# SAME51_PINOUT.net
KiCad netlist of a schematic drawn in Altium Designer
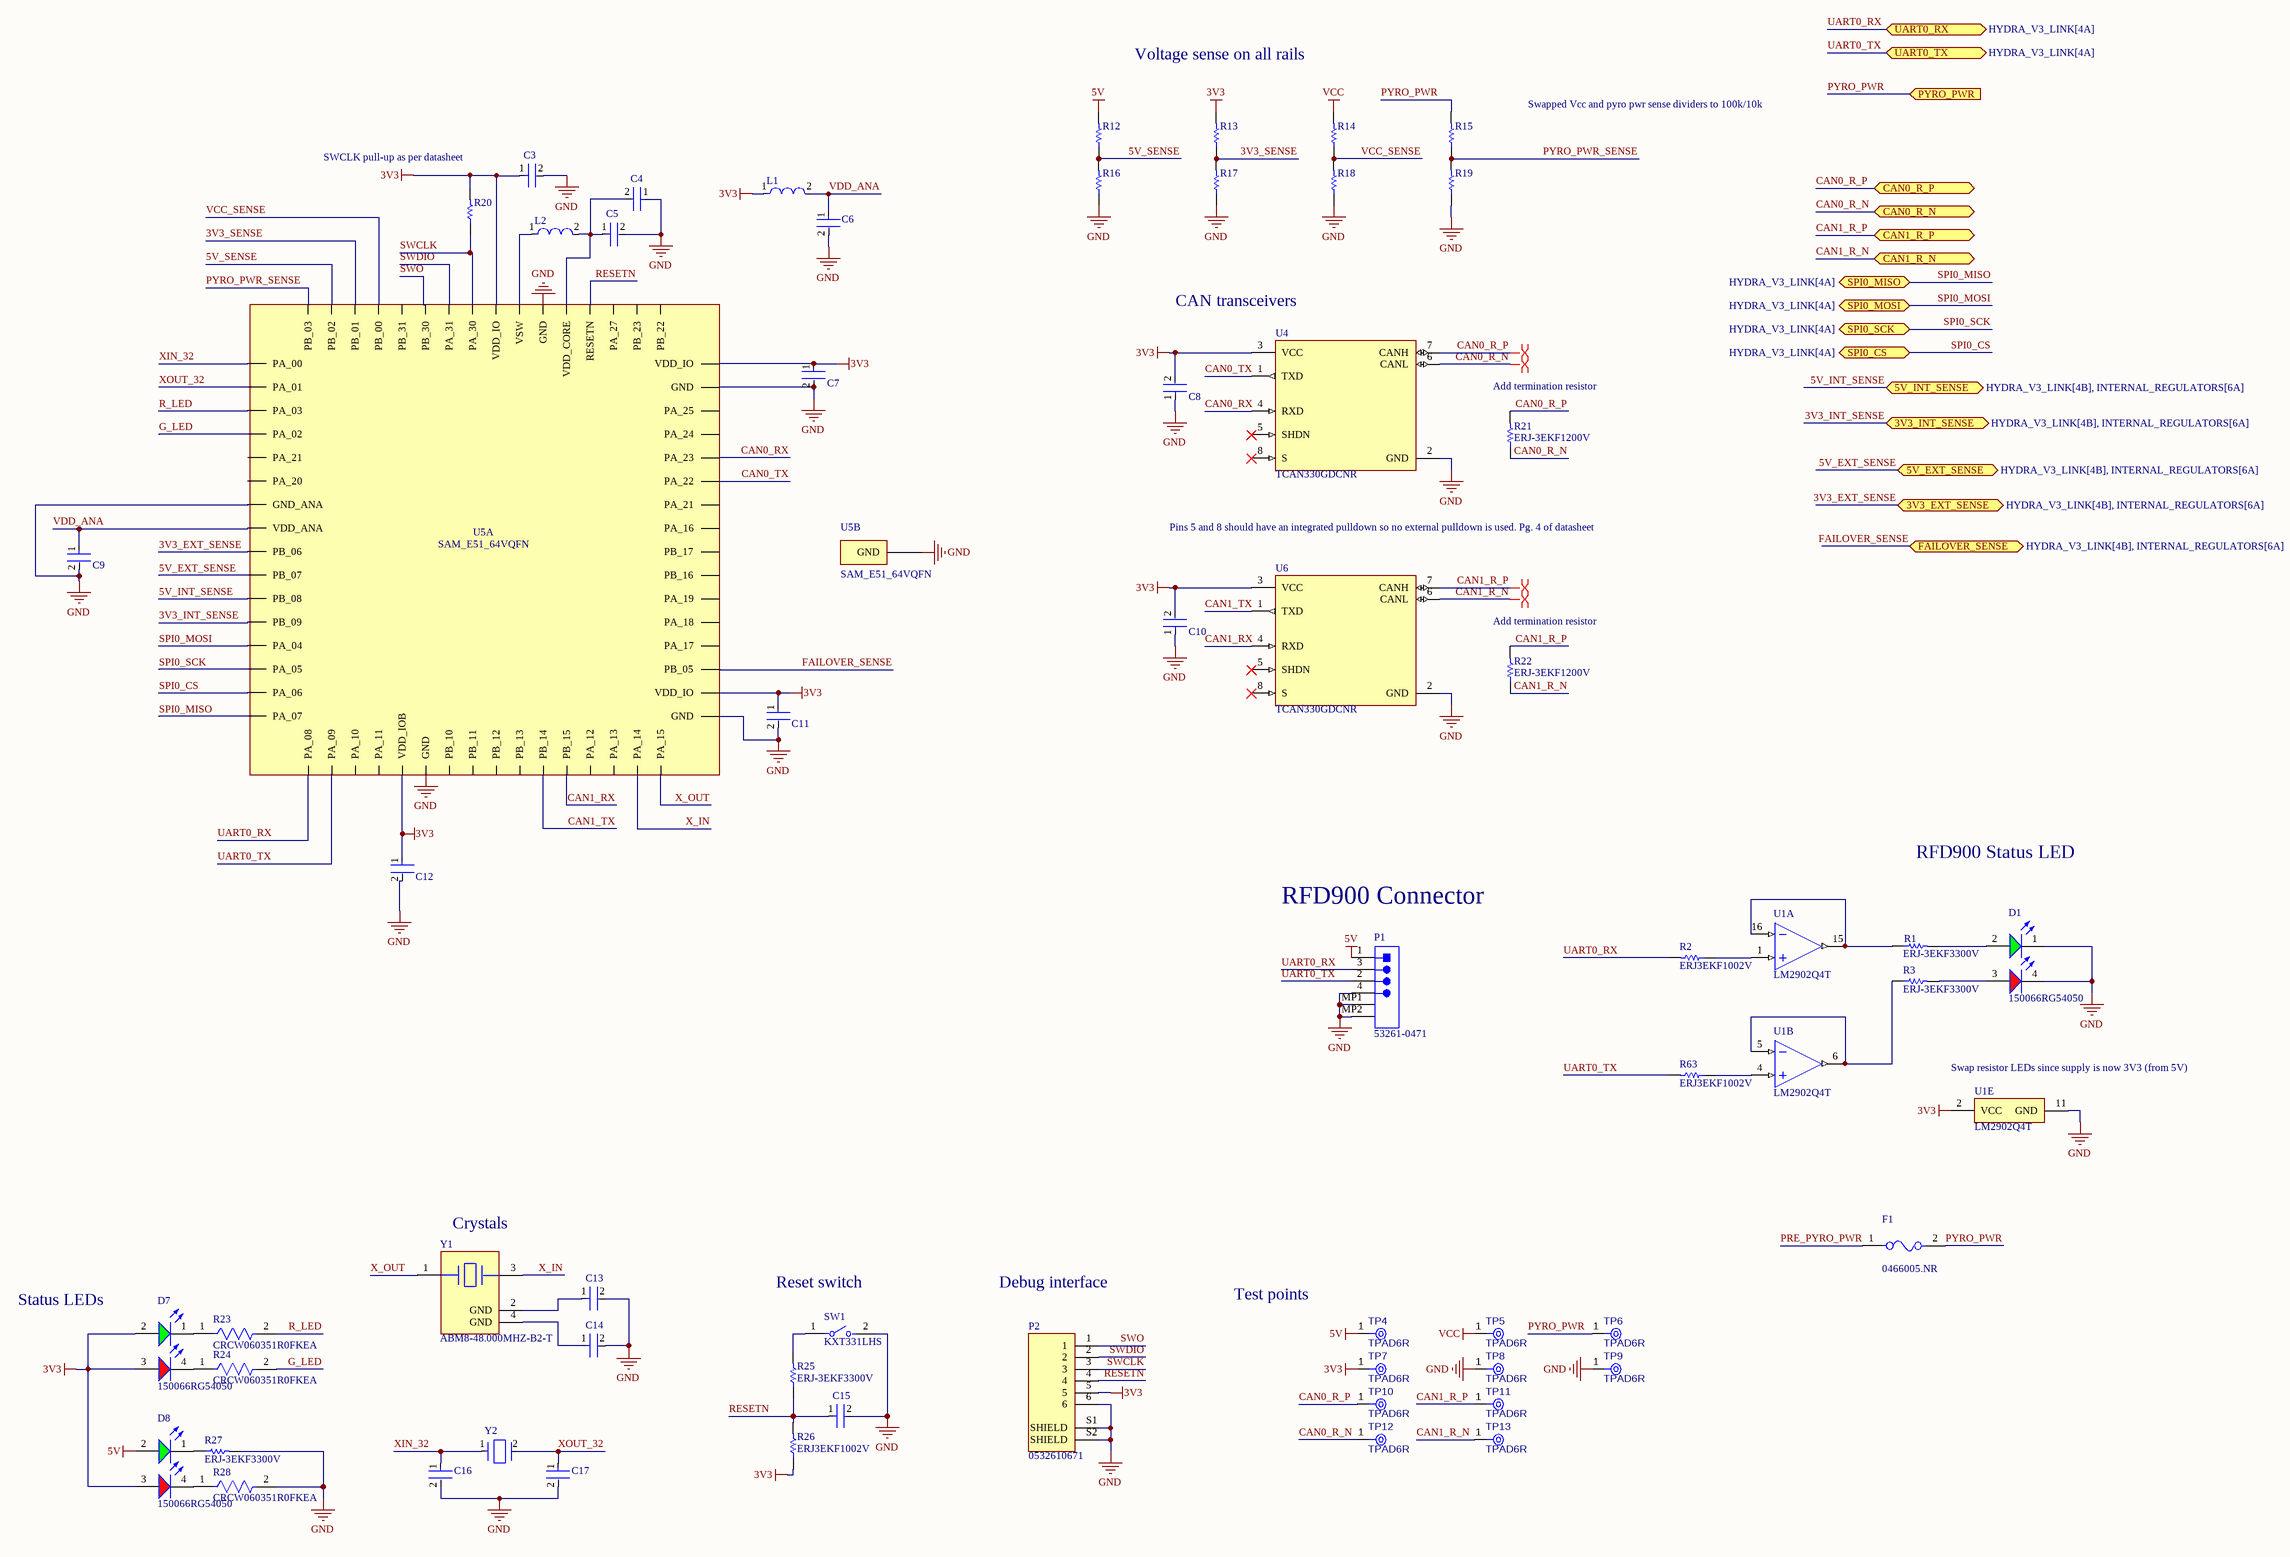
[diagram p0: SAME51_PINOUT.SchDoc]

(export (version "E")
  (design (tool "Eeschema 10.0.6"))
  (components
    (comp (ref "C3")
      (value "C0402C104K8PACTU")
      (footprint "FP-C0402-BB-MFG")
      (description "CAP CER 0.1UF 10V X5R 0402")
      (fields (field (name "MANUFACTURER") "Kemet") (field (name "TOLERANCE") "0.1"))
      (libsource (lib "Altium Content Vault") (part "b4654b650e69147ec39a6b967a45e02"))
    )
    (comp (ref "C4")
      (value "GRM155R60J475ME47D")
      (footprint "FP-GRM155-0_1-IPC_B")
      (description "Chip Multilayer Ceramic Capacitors for General Purpose, 0402, 4.7uF, X5R, 15%, 20%, 6.3V")
      (fields (field (name "VOLTAGE") "6.3V") (field (name "TOLERANCE") "20%"))
      (libsource (lib "Altium Content Vault") (part "11868f565c42a9108669ba33697ecf6"))
    )
    (comp (ref "C5")
      (value "C0402C104K8PACTU")
      (footprint "FP-C0402-BB-MFG")
      (description "CAP CER 0.1UF 10V X5R 0402")
      (fields (field (name "MANUFACTURER") "Kemet") (field (name "TOLERANCE") "0.1"))
      (libsource (lib "Altium Content Vault") (part "b4654b650e69147ec39a6b967a45e02"))
    )
    (comp (ref "C6")
      (value "C0805C106K8PACTU")
      (footprint "FP-C0805C-DG-MFG")
      (description "CAP CER 10UF 10V X5R 0805")
      (fields (field (name "TOLERANCE") "10%") (field (name "MANUFACTURER") "Kemet"))
      (libsource (lib "Altium Content Vault") (part "11868f565c42a9108669ba33697ecf6"))
    )
    (comp (ref "C7")
      (value "C0402C104K8PACTU")
      (footprint "FP-C0402-BB-MFG")
      (description "CAP CER 0.1UF 10V X5R 0402")
      (fields (field (name "MANUFACTURER") "Kemet") (field (name "TOLERANCE") "0.1"))
      (libsource (lib "Altium Content Vault") (part "b4654b650e69147ec39a6b967a45e02"))
    )
    (comp (ref "C8")
      (value "C0402C104K8PACTU")
      (footprint "FP-C0402-BB-MFG")
      (description "CAP CER 0.1UF 10V X5R 0402")
      (fields (field (name "MANUFACTURER") "Kemet") (field (name "TOLERANCE") "0.1"))
      (libsource (lib "Altium Content Vault") (part "b4654b650e69147ec39a6b967a45e02"))
    )
    (comp (ref "C9")
      (value "C0402C104K8PACTU")
      (footprint "FP-C0402-BB-MFG")
      (description "CAP CER 0.1UF 10V X5R 0402")
      (fields (field (name "MANUFACTURER") "Kemet") (field (name "TOLERANCE") "0.1"))
      (libsource (lib "Altium Content Vault") (part "b4654b650e69147ec39a6b967a45e02"))
    )
    (comp (ref "C10")
      (value "C0402C104K8PACTU")
      (footprint "FP-C0402-BB-MFG")
      (description "CAP CER 0.1UF 10V X5R 0402")
      (fields (field (name "MANUFACTURER") "Kemet") (field (name "TOLERANCE") "0.1"))
      (libsource (lib "Altium Content Vault") (part "b4654b650e69147ec39a6b967a45e02"))
    )
    (comp (ref "C11")
      (value "C0402C104K8PACTU")
      (footprint "FP-C0402-BB-MFG")
      (description "CAP CER 0.1UF 10V X5R 0402")
      (fields (field (name "MANUFACTURER") "Kemet") (field (name "TOLERANCE") "0.1"))
      (libsource (lib "Altium Content Vault") (part "b4654b650e69147ec39a6b967a45e02"))
    )
    (comp (ref "C12")
      (value "C0402C104K8PACTU")
      (footprint "FP-C0402-BB-MFG")
      (description "CAP CER 0.1UF 10V X5R 0402")
      (fields (field (name "MANUFACTURER") "Kemet") (field (name "TOLERANCE") "0.1"))
      (libsource (lib "Altium Content Vault") (part "b4654b650e69147ec39a6b967a45e02"))
    )
    (comp (ref "C13")
      (value "08051A6R8CAT2A")
      (footprint "FP-0805-L_2_01_0_2-W_1_25-MFG")
      (description "General Purpose Ceramic Capacitor, 0805, 6.8pF, 0.25pF, C0G, 30ppm/°C, 100V")
      (fields (field (name "VOLTAGE") "100V") (field (name "TOLERANCE") "5%"))
      (libsource (lib "Altium Content Vault") (part "02cd4be3c70576c341d710602a673aa"))
    )
    (comp (ref "C14")
      (value "08051A6R8CAT2A")
      (footprint "FP-0805-L_2_01_0_2-W_1_25-MFG")
      (description "General Purpose Ceramic Capacitor, 0805, 6.8pF, 0.25pF, C0G, 30ppm/°C, 100V")
      (fields (field (name "VOLTAGE") "100V") (field (name "TOLERANCE") "5%"))
      (libsource (lib "Altium Content Vault") (part "02cd4be3c70576c341d710602a673aa"))
    )
    (comp (ref "C15")
      (value "C0402C104K8PACTU")
      (footprint "FP-C0402-BB-MFG")
      (description "CAP CER 0.1UF 10V X5R 0402")
      (fields (field (name "MANUFACTURER") "Kemet") (field (name "TOLERANCE") "0.1"))
      (libsource (lib "Altium Content Vault") (part "b4654b650e69147ec39a6b967a45e02"))
    )
    (comp (ref "C16")
      (value "C0805C180J5GACTU")
      (footprint "FP-C0805C-DN-MFG")
      (description "CAP CER 18PF 50V C0G/NP0 0805")
      (fields
        (field (name "OCTOPART") "https://octopart.com/c0805c180j5gactu-kemet-144810")
        (field (name "TOLERANCE") "0.05")
      )
      (libsource (lib "Altium Content Vault") (part "b4654b650e69147ec39a6b967a45e02"))
    )
    (comp (ref "C17")
      (value "C0805C180J5GACTU")
      (footprint "FP-C0805C-DN-MFG")
      (description "CAP CER 18PF 50V C0G/NP0 0805")
      (fields
        (field (name "OCTOPART") "https://octopart.com/c0805c180j5gactu-kemet-144810")
        (field (name "TOLERANCE") "0.05")
      )
      (libsource (lib "Altium Content Vault") (part "b4654b650e69147ec39a6b967a45e02"))
    )
    (comp (ref "D1")
      (value "150066RG54050")
      (footprint "WL-SBCD_0606")
      (description "Led, Red/Grn, 180Mcd/230Mcd, 624Nm/525Nm Rohs Compliant: Yes")
      (libsource (lib "uORocketry Hardware") (part "WL-SBCD_0606_Red & Green"))
    )
    (comp (ref "D7")
      (value "150066RG54050")
      (footprint "WL-SBCD_0606")
      (description "Led, Red/Grn, 180Mcd/230Mcd, 624Nm/525Nm Rohs Compliant: Yes")
      (libsource (lib "uORocketry Hardware") (part "WL-SBCD_0606_Red & Green"))
    )
    (comp (ref "D8")
      (value "150066RG54050")
      (footprint "WL-SBCD_0606")
      (description "Led, Red/Grn, 180Mcd/230Mcd, 624Nm/525Nm Rohs Compliant: Yes")
      (libsource (lib "uORocketry Hardware") (part "WL-SBCD_0606_Red & Green"))
    )
    (comp (ref "F1")
      (value "0466005.NR")
      (footprint "FP-0466-MFG")
      (description "FUSE BOARD MNT 5A 32VAC/VDC 1206")
      (fields
        (field (name "OCTOPART") "https://octopart.com/0466005.nr-littelfuse-143206")
        (field (name "MANUFACTURER") "Littelfuse Inc")
      )
      (libsource (lib "Altium Content Vault") (part "5bcf9b9f640e542cf0359d10258e979"))
    )
    (comp (ref "L1")
      (value "NR6028T100M")
      (footprint "FP-NR6028-MFG")
      (description "SMD Power Inductors 10uH ±20% 1.9A 84.5mΩ")
      (fields (field (name "TOLERANCE") "20%"))
      (libsource (lib "Altium Content Vault") (part "725321dda6339637d4d059423bc1c3c"))
    )
    (comp (ref "L2")
      (value "NR6028T100M")
      (footprint "FP-NR6028-MFG")
      (description "SMD Power Inductors 10uH ±20% 1.9A 84.5mΩ")
      (fields (field (name "TOLERANCE") "20%"))
      (libsource (lib "Altium Content Vault") (part "725321dda6339637d4d059423bc1c3c"))
    )
    (comp (ref "P1")
      (value "53261-0471")
      (footprint "MOLEX-53261-0471_V")
      (description "Male Header, Pitch 1.25 mm, 1 x 4 Position, Height 3.4 mm, -40 to 85 degC, RoHS, Tape and Reel")
      (fields (field (name "MANUFACTURER") "Molex"))
      (libsource (lib "Altium Content Vault") (part "CN-1P-2M-R4_A"))
    )
    (comp (ref "P2")
      (value "0532610671")
      (footprint "0532610671-Footprint-1")
      (description "Conn Shrouded Header (4 Sides) HDR 6 POS 1.25mm Solder RA Side Entry SMD PicoBlade™ T/R")
      (libsource (lib "uORocketry Hardware") (part "0532610671"))
    )
    (comp (ref "R1")
      (value "ERJ-3EKF3300V")
      (footprint "RESC1608X55X30LL15T15")
      (description "Chip Resistor, 330 Ohm, +/- 1%, 0.1 W, -55 to 155 degC, 0603 (1608 Metric), RoHS, Tape and Reel")
      (libsource (lib "Altium Content Vault") (part "RES-2"))
    )
    (comp (ref "R2")
      (value "ERJ3EKF1002V")
      (footprint "RESC1609X55X30LL15T15")
      (description "Chip Resistor, 10 KOhm, +/- 1%, 0.1 W, -55 to 155 degC, 0603 (1608 Metric), RoHS, Tape and Reel")
      (fields (field (name "TOLERANCE") "1%") (field (name "MANUFACTURER") "Panasonic"))
      (libsource (lib "Altium Content Vault") (part "RES-2"))
    )
    (comp (ref "R3")
      (value "ERJ-3EKF3300V")
      (footprint "RESC1608X55X30LL15T15")
      (description "Chip Resistor, 330 Ohm, +/- 1%, 0.1 W, -55 to 155 degC, 0603 (1608 Metric), RoHS, Tape and Reel")
      (libsource (lib "Altium Content Vault") (part "RES-2"))
    )
    (comp (ref "R12")
      (value "ERJ3EKF1002V")
      (footprint "RESC1609X55X30LL15T15")
      (description "Chip Resistor, 10 KOhm, +/- 1%, 0.1 W, -55 to 155 degC, 0603 (1608 Metric), RoHS, Tape and Reel")
      (fields (field (name "TOLERANCE") "1%") (field (name "MANUFACTURER") "Panasonic"))
      (libsource (lib "Altium Content Vault") (part "RES-2"))
    )
    (comp (ref "R13")
      (value "ERJ3EKF1002V")
      (footprint "RESC1609X55X30LL15T15")
      (description "Chip Resistor, 10 KOhm, +/- 1%, 0.1 W, -55 to 155 degC, 0603 (1608 Metric), RoHS, Tape and Reel")
      (fields (field (name "TOLERANCE") "1%") (field (name "MANUFACTURER") "Panasonic"))
      (libsource (lib "Altium Content Vault") (part "RES-2"))
    )
    (comp (ref "R14")
      (value "ERJ-3EKF1003V")
      (footprint "RESC1608X55X30ML15T15")
      (fields (field (name "MANUFACTURER") "Panasonic"))
      (libsource (lib "Altium Content Vault") (part "RES"))
    )
    (comp (ref "R15")
      (value "ERJ-3EKF1003V")
      (footprint "RESC1608X55X30ML15T15")
      (fields (field (name "MANUFACTURER") "Panasonic"))
      (libsource (lib "Altium Content Vault") (part "RES"))
    )
    (comp (ref "R16")
      (value "ERJ3EKF1002V")
      (footprint "RESC1609X55X30LL15T15")
      (description "Chip Resistor, 10 KOhm, +/- 1%, 0.1 W, -55 to 155 degC, 0603 (1608 Metric), RoHS, Tape and Reel")
      (fields (field (name "TOLERANCE") "1%") (field (name "MANUFACTURER") "Panasonic"))
      (libsource (lib "Altium Content Vault") (part "RES-2"))
    )
    (comp (ref "R17")
      (value "ERJ3EKF1002V")
      (footprint "RESC1609X55X30LL15T15")
      (description "Chip Resistor, 10 KOhm, +/- 1%, 0.1 W, -55 to 155 degC, 0603 (1608 Metric), RoHS, Tape and Reel")
      (fields (field (name "TOLERANCE") "1%") (field (name "MANUFACTURER") "Panasonic"))
      (libsource (lib "Altium Content Vault") (part "RES-2"))
    )
    (comp (ref "R18")
      (value "ERJ3EKF1002V")
      (footprint "RESC1609X55X30LL15T15")
      (description "Chip Resistor, 10 KOhm, +/- 1%, 0.1 W, -55 to 155 degC, 0603 (1608 Metric), RoHS, Tape and Reel")
      (fields (field (name "TOLERANCE") "1%") (field (name "MANUFACTURER") "Panasonic"))
      (libsource (lib "Altium Content Vault") (part "RES-2"))
    )
    (comp (ref "R19")
      (value "ERJ3EKF1002V")
      (footprint "RESC1609X55X30LL15T15")
      (description "Chip Resistor, 10 KOhm, +/- 1%, 0.1 W, -55 to 155 degC, 0603 (1608 Metric), RoHS, Tape and Reel")
      (fields (field (name "TOLERANCE") "1%") (field (name "MANUFACTURER") "Panasonic"))
      (libsource (lib "Altium Content Vault") (part "RES-2"))
    )
    (comp (ref "R20")
      (value "ERJ3EKF1002V")
      (footprint "RESC1609X55X30LL15T15")
      (description "Chip Resistor, 10 KOhm, +/- 1%, 0.1 W, -55 to 155 degC, 0603 (1608 Metric), RoHS, Tape and Reel")
      (fields (field (name "TOLERANCE") "1%") (field (name "MANUFACTURER") "Panasonic"))
      (libsource (lib "Altium Content Vault") (part "RES-2"))
    )
    (comp (ref "R21")
      (value "ERJ-3EKF1200V")
      (footprint "RESC1609X55X30ML15T15")
      (description "Chip Resistor, 120 Ohm, +/- 1%, 0.1 W, -55 to 155 degC, 0603 (1608 Metric), RoHS, Tape and Reel")
      (fields (field (name "TOLERANCE") "1%") (field (name "MANUFACTURER") "Panasonic"))
      (libsource (lib "Altium Content Vault") (part "RES-2"))
    )
    (comp (ref "R22")
      (value "ERJ-3EKF1200V")
      (footprint "RESC1609X55X30ML15T15")
      (description "Chip Resistor, 120 Ohm, +/- 1%, 0.1 W, -55 to 155 degC, 0603 (1608 Metric), RoHS, Tape and Reel")
      (fields (field (name "TOLERANCE") "1%") (field (name "MANUFACTURER") "Panasonic"))
      (libsource (lib "Altium Content Vault") (part "RES-2"))
    )
    (comp (ref "R23")
      (value "CRCW060351R0FKEA")
      (footprint "FP-CRCW0603-e3-MFG")
      (description "RES Thick Film, 51Ω, 1%, 0.1W, 100ppm/°C, 0603")
      (fields (field (name "TOLERANCE") "1%"))
      (libsource (lib "Altium Content Vault") (part "1029c3af85768c4190bb7ad29bc67b5"))
    )
    (comp (ref "R24")
      (value "CRCW060351R0FKEA")
      (footprint "FP-CRCW0603-e3-MFG")
      (description "RES Thick Film, 51Ω, 1%, 0.1W, 100ppm/°C, 0603")
      (fields (field (name "TOLERANCE") "1%"))
      (libsource (lib "Altium Content Vault") (part "1029c3af85768c4190bb7ad29bc67b5"))
    )
    (comp (ref "R25")
      (value "ERJ-3EKF3300V")
      (footprint "RESC1608X55X30LL15T15")
      (description "Chip Resistor, 330 Ohm, +/- 1%, 0.1 W, -55 to 155 degC, 0603 (1608 Metric), RoHS, Tape and Reel")
      (libsource (lib "Altium Content Vault") (part "RES-2"))
    )
    (comp (ref "R26")
      (value "ERJ3EKF1002V")
      (footprint "RESC1609X55X30LL15T15")
      (description "Chip Resistor, 10 KOhm, +/- 1%, 0.1 W, -55 to 155 degC, 0603 (1608 Metric), RoHS, Tape and Reel")
      (fields (field (name "TOLERANCE") "1%") (field (name "MANUFACTURER") "Panasonic"))
      (libsource (lib "Altium Content Vault") (part "RES-2"))
    )
    (comp (ref "R27")
      (value "ERJ-3EKF3300V")
      (footprint "RESC1608X55X30LL15T15")
      (description "Chip Resistor, 330 Ohm, +/- 1%, 0.1 W, -55 to 155 degC, 0603 (1608 Metric), RoHS, Tape and Reel")
      (libsource (lib "Altium Content Vault") (part "RES-2"))
    )
    (comp (ref "R28")
      (value "CRCW060351R0FKEA")
      (footprint "FP-CRCW0603-e3-MFG")
      (description "RES Thick Film, 51Ω, 1%, 0.1W, 100ppm/°C, 0603")
      (fields (field (name "TOLERANCE") "1%"))
      (libsource (lib "Altium Content Vault") (part "1029c3af85768c4190bb7ad29bc67b5"))
    )
    (comp (ref "R63")
      (value "ERJ3EKF1002V")
      (footprint "RESC1609X55X30LL15T15")
      (description "Chip Resistor, 10 KOhm, +/- 1%, 0.1 W, -55 to 155 degC, 0603 (1608 Metric), RoHS, Tape and Reel")
      (fields (field (name "TOLERANCE") "1%") (field (name "MANUFACTURER") "Panasonic"))
      (libsource (lib "Altium Content Vault") (part "RES-2"))
    )
    (comp (ref "SW1")
      (value "KXT331LHS")
      (footprint "FP-KXT331LHS-MFG")
      (description "SWITCH TACTILE SPST-NO 0.02A 15V")
      (libsource (lib "Altium Content Vault") (part "bb27bde45df87f1f469753f287ef5ae"))
    )
    (comp (ref "TP4")
      (value "TPAD6R")
      (footprint "TP06R")
      (description "0.6mm round")
      (libsource (lib "uORocketry Hardware") (part "CMP-001-0001-4"))
    )
    (comp (ref "TP5")
      (value "TPAD6R")
      (footprint "TP06R")
      (description "0.6mm round")
      (libsource (lib "uORocketry Hardware") (part "CMP-001-0001-4"))
    )
    (comp (ref "TP6")
      (value "TPAD6R")
      (footprint "TP06R")
      (description "0.6mm round")
      (libsource (lib "uORocketry Hardware") (part "CMP-001-0001-4"))
    )
    (comp (ref "TP7")
      (value "TPAD6R")
      (footprint "TP06R")
      (description "0.6mm round")
      (libsource (lib "uORocketry Hardware") (part "CMP-001-0001-4"))
    )
    (comp (ref "TP8")
      (value "TPAD6R")
      (footprint "TP06R")
      (description "0.6mm round")
      (libsource (lib "uORocketry Hardware") (part "CMP-001-0001-4"))
    )
    (comp (ref "TP9")
      (value "TPAD6R")
      (footprint "TP06R")
      (description "0.6mm round")
      (libsource (lib "uORocketry Hardware") (part "CMP-001-0001-4"))
    )
    (comp (ref "TP10")
      (value "TPAD6R")
      (footprint "TP06R")
      (description "0.6mm round")
      (libsource (lib "uORocketry Hardware") (part "CMP-001-0001-4"))
    )
    (comp (ref "TP11")
      (value "TPAD6R")
      (footprint "TP06R")
      (description "0.6mm round")
      (libsource (lib "uORocketry Hardware") (part "CMP-001-0001-4"))
    )
    (comp (ref "TP12")
      (value "TPAD6R")
      (footprint "TP06R")
      (description "0.6mm round")
      (libsource (lib "uORocketry Hardware") (part "CMP-001-0001-4"))
    )
    (comp (ref "TP13")
      (value "TPAD6R")
      (footprint "TP06R")
      (description "0.6mm round")
      (libsource (lib "uORocketry Hardware") (part "CMP-001-0001-4"))
    )
    (comp (ref "U1")
      (value "LM2902Q4T")
      (footprint "LM2902Q4T-Footprint-1")
      (description "LM2902 Series 30 V 1.3 MHz Low-Power Quad Operational Amplifier - QFN-16 (3x3)")
      (libsource (lib "uORocketry Hardware") (part "LM2902Q4T"))
    )
    (comp (ref "U4")
      (value "TCAN330GDCNR")
      (footprint "FP-DCN0008A-MFG")
      (description "IC TRANSCEIVER 1/1 SOT23-8")
      (libsource (lib "Altium Content Vault") (part "22681b49c22ad38c6a4e12e04c36c7a"))
    )
    (comp (ref "U5")
      (value "SAM_E51_64VQFN")
      (footprint "SAM_E51_64VQFN-Footprint-1")
      (description "Rudimentary symbol and footprint for the SAM E51 microcontroller")
      (libsource (lib "") (part "SAM_E51_64VQFN-Symbol-1_1"))
    )
    (comp (ref "U6")
      (value "TCAN330GDCNR")
      (footprint "FP-DCN0008A-MFG")
      (description "IC TRANSCEIVER 1/1 SOT23-8")
      (libsource (lib "Altium Content Vault") (part "22681b49c22ad38c6a4e12e04c36c7a"))
    )
    (comp (ref "Y1")
      (value "ABM8-48.000MHZ-B2-T")
      (footprint "FP-ABM8-MFG")
      (description "Crystal 48MHz ±20ppm 18pF SMD-4 3.2mm x 2.5mm")
      (fields (field (name "TOLERANCE") "20ppm"))
      (libsource (lib "Altium Content Vault") (part "dfdb7f9a12507849fb681da9a70121c"))
    )
    (comp (ref "Y2")
      (value "ECS-.327-12.5-1210-TR")
      (footprint "FP-ECX-1210-MFG")
      (description "CRYSTAL 32.7680KHZ 12.5PF SMD")
      (fields
        (field (name "OCTOPART") "https://octopart.com/ecs-.327-12.5-1210-tr-ecs+international-81221340")
        (field (name "TOLERANCE") "20ppm")
      )
      (libsource (lib "Altium Content Vault") (part "99724985039315a44fd0d1401b84e49"))
    )
  )
  (nets
    (net (code "1") (name "/3V3_EXT_SENSE") (class "Default")
      (node (ref "U5") (pin "9") (pinfunction "PB_06_9") (pintype "passive"))
    )
    (net (code "2") (name "/3V3_INT_SENSE") (class "Default")
      (node (ref "U5") (pin "12") (pinfunction "PB_09_12") (pintype "passive"))
    )
    (net (code "3") (name "/3V3_SENSE") (class "Default")
      (node (ref "R13") (pin "1") (pinfunction "1_1") (pintype "passive"))
      (node (ref "R17") (pin "2") (pinfunction "2_2") (pintype "passive"))
      (node (ref "U5") (pin "62") (pinfunction "PB_01_62") (pintype "passive"))
    )
    (net (code "4") (name "/5V_EXT_SENSE") (class "Default")
      (node (ref "U5") (pin "10") (pinfunction "PB_07_10") (pintype "passive"))
    )
    (net (code "5") (name "/5V_INT_SENSE") (class "Default")
      (node (ref "U5") (pin "11") (pinfunction "PB_08_11") (pintype "passive"))
    )
    (net (code "6") (name "/5V_SENSE") (class "Default")
      (node (ref "R12") (pin "1") (pinfunction "1_1") (pintype "passive"))
      (node (ref "R16") (pin "2") (pinfunction "2_2") (pintype "passive"))
      (node (ref "U5") (pin "63") (pinfunction "PB_02_63") (pintype "passive"))
    )
    (net (code "8") (name "/CAN0_RX") (class "Default")
      (node (ref "U4") (pin "4") (pinfunction "RXD_4") (pintype "input"))
      (node (ref "U5") (pin "44") (pinfunction "PA_23_44") (pintype "passive"))
    )
    (net (code "9") (name "/CAN0_R_N") (class "Default")
      (node (ref "R21") (pin "1") (pinfunction "1_1") (pintype "passive"))
      (node (ref "TP12") (pin "1") (pinfunction "TP_1") (pintype "passive"))
      (node (ref "U4") (pin "6") (pinfunction "CANL_6") (pintype "bidirectional"))
    )
    (net (code "10") (name "/CAN0_R_P") (class "Default")
      (node (ref "R21") (pin "2") (pinfunction "2_2") (pintype "passive"))
      (node (ref "TP10") (pin "1") (pinfunction "TP_1") (pintype "passive"))
      (node (ref "U4") (pin "7") (pinfunction "CANH_7") (pintype "bidirectional"))
    )
    (net (code "11") (name "/CAN0_TX") (class "Default")
      (node (ref "U4") (pin "1") (pinfunction "TXD_1") (pintype "output"))
      (node (ref "U5") (pin "43") (pinfunction "PA_22_43") (pintype "passive"))
    )
    (net (code "12") (name "/CAN1_RX") (class "Default")
      (node (ref "U5") (pin "28") (pinfunction "PB_15_28") (pintype "passive"))
      (node (ref "U6") (pin "4") (pinfunction "RXD_4") (pintype "input"))
    )
    (net (code "13") (name "/CAN1_R_N") (class "Default")
      (node (ref "R22") (pin "1") (pinfunction "1_1") (pintype "passive"))
      (node (ref "TP13") (pin "1") (pinfunction "TP_1") (pintype "passive"))
      (node (ref "U6") (pin "6") (pinfunction "CANL_6") (pintype "bidirectional"))
    )
    (net (code "14") (name "/CAN1_R_P") (class "Default")
      (node (ref "R22") (pin "2") (pinfunction "2_2") (pintype "passive"))
      (node (ref "TP11") (pin "1") (pinfunction "TP_1") (pintype "passive"))
      (node (ref "U6") (pin "7") (pinfunction "CANH_7") (pintype "bidirectional"))
    )
    (net (code "15") (name "/CAN1_TX") (class "Default")
      (node (ref "U5") (pin "27") (pinfunction "PB_14_27") (pintype "passive"))
      (node (ref "U6") (pin "1") (pinfunction "TXD_1") (pintype "output"))
    )
    (net (code "16") (name "/FAILOVER_SENSE") (class "Default")
      (node (ref "U5") (pin "6") (pinfunction "PB_05_6") (pintype "passive"))
    )
    (net (code "17") (name "/G_LED") (class "Default")
      (node (ref "R24") (pin "2") (pinfunction "2_2") (pintype "passive"))
      (node (ref "U5") (pin "3") (pinfunction "PA_02_3") (pintype "passive"))
    )
    (net (code "18") (name "/PRE_PYRO_PWR") (class "Default")
      (node (ref "F1") (pin "1") (pinfunction "1_1") (pintype "passive"))
    )
    (net (code "19") (name "/PYRO_PWR") (class "Default")
      (node (ref "F1") (pin "2") (pinfunction "2_2") (pintype "passive"))
      (node (ref "R15") (pin "2") (pinfunction "2_2") (pintype "passive"))
      (node (ref "TP6") (pin "1") (pinfunction "TP_1") (pintype "passive"))
    )
    (net (code "20") (name "/PYRO_PWR_SENSE") (class "Default")
      (node (ref "R15") (pin "1") (pinfunction "1_1") (pintype "passive"))
      (node (ref "R19") (pin "2") (pinfunction "2_2") (pintype "passive"))
      (node (ref "U5") (pin "64") (pinfunction "PB_03_64") (pintype "passive"))
    )
    (net (code "21") (name "/RESETN") (class "Default")
      (node (ref "C15") (pin "1") (pinfunction "1_1") (pintype "passive"))
      (node (ref "P2") (pin "4") (pinfunction "4_4") (pintype "passive"))
      (node (ref "R25") (pin "1") (pinfunction "1_1") (pintype "passive"))
      (node (ref "R26") (pin "2") (pinfunction "2_2") (pintype "passive"))
      (node (ref "U5") (pin "52") (pinfunction "RESETN_52") (pintype "passive"))
    )
    (net (code "22") (name "/R_LED") (class "Default")
      (node (ref "R23") (pin "2") (pinfunction "2_2") (pintype "passive"))
      (node (ref "U5") (pin "4") (pinfunction "PA_03_4") (pintype "passive"))
    )
    (net (code "23") (name "/SPI0_CS") (class "Default")
      (node (ref "U5") (pin "15") (pinfunction "PA_06_15") (pintype "passive"))
    )
    (net (code "24") (name "/SPI0_MISO") (class "Default")
      (node (ref "U5") (pin "16") (pinfunction "PA_07_16") (pintype "passive"))
    )
    (net (code "25") (name "/SPI0_MOSI") (class "Default")
      (node (ref "U5") (pin "13") (pinfunction "PA_04_13") (pintype "passive"))
    )
    (net (code "26") (name "/SPI0_SCK") (class "Default")
      (node (ref "U5") (pin "14") (pinfunction "PA_05_14") (pintype "passive"))
    )
    (net (code "27") (name "/SWCLK") (class "Default")
      (node (ref "P2") (pin "3") (pinfunction "3_3") (pintype "passive"))
      (node (ref "R20") (pin "1") (pinfunction "1_1") (pintype "passive"))
      (node (ref "U5") (pin "57") (pinfunction "PA_30_57") (pintype "passive"))
    )
    (net (code "28") (name "/SWDIO") (class "Default")
      (node (ref "P2") (pin "2") (pinfunction "2_2") (pintype "passive"))
      (node (ref "U5") (pin "58") (pinfunction "PA_31_58") (pintype "passive"))
    )
    (net (code "29") (name "/SWO") (class "Default")
      (node (ref "P2") (pin "1") (pinfunction "1_1") (pintype "passive"))
      (node (ref "U5") (pin "59") (pinfunction "PB_30_59") (pintype "passive"))
    )
    (net (code "30") (name "/UART0_RX") (class "Default")
      (node (ref "P1") (pin "3") (pinfunction "3_3") (pintype "passive"))
      (node (ref "R2") (pin "2") (pinfunction "2_2") (pintype "passive"))
      (node (ref "U5") (pin "17") (pinfunction "PA_08_17") (pintype "passive"))
    )
    (net (code "31") (name "/UART0_TX") (class "Default")
      (node (ref "P1") (pin "2") (pinfunction "2_2") (pintype "passive"))
      (node (ref "R63") (pin "2") (pinfunction "2_2") (pintype "passive"))
      (node (ref "U5") (pin "18") (pinfunction "PA_09_18") (pintype "passive"))
    )
    (net (code "32") (name "/VCC_SENSE") (class "Default")
      (node (ref "R14") (pin "1") (pinfunction "1_1") (pintype "passive"))
      (node (ref "R18") (pin "2") (pinfunction "2_2") (pintype "passive"))
      (node (ref "U5") (pin "61") (pinfunction "PB_00_61") (pintype "passive"))
    )
    (net (code "33") (name "/VDD_ANA") (class "Default")
      (node (ref "C6") (pin "1") (pinfunction "1_1") (pintype "passive"))
      (node (ref "C9") (pin "1") (pinfunction "1_1") (pintype "passive"))
      (node (ref "L1") (pin "2") (pinfunction "2_2") (pintype "passive"))
      (node (ref "U5") (pin "8") (pinfunction "VDD_ANA_8") (pintype "passive"))
    )
    (net (code "34") (name "/XIN_32") (class "Default")
      (node (ref "C16") (pin "1") (pinfunction "1_1") (pintype "passive"))
      (node (ref "U5") (pin "1") (pinfunction "PA_00_1") (pintype "passive"))
      (node (ref "Y2") (pin "1") (pinfunction "In/Out_1") (pintype "passive"))
    )
    (net (code "35") (name "/XOUT_32") (class "Default")
      (node (ref "C17") (pin "1") (pinfunction "1_1") (pintype "passive"))
      (node (ref "U5") (pin "2") (pinfunction "PA_01_2") (pintype "passive"))
      (node (ref "Y2") (pin "2") (pinfunction "Out/In_2") (pintype "passive"))
    )
    (net (code "36") (name "/X_IN") (class "Default")
      (node (ref "U5") (pin "31") (pinfunction "PA_14_31") (pintype "passive"))
      (node (ref "Y1") (pin "3") (pinfunction "3_3") (pintype "passive"))
    )
    (net (code "37") (name "/X_OUT") (class "Default")
      (node (ref "U5") (pin "32") (pinfunction "PA_15_32") (pintype "passive"))
      (node (ref "Y1") (pin "1") (pinfunction "1_1") (pintype "passive"))
    )
    (net (code "38") (name "3V3") (class "Default")
      (node (ref "C10") (pin "2") (pinfunction "2_2") (pintype "passive"))
      (node (ref "C11") (pin "1") (pinfunction "1_1") (pintype "passive"))
      (node (ref "C12") (pin "1") (pinfunction "1_1") (pintype "passive"))
      (node (ref "C3") (pin "1") (pinfunction "1_1") (pintype "passive"))
      (node (ref "C7") (pin "1") (pinfunction "1_1") (pintype "passive"))
      (node (ref "C8") (pin "2") (pinfunction "2_2") (pintype "passive"))
      (node (ref "D7") (pin "2") (pinfunction "A_2") (pintype "passive"))
      (node (ref "D7") (pin "3") (pinfunction "A_3") (pintype "passive"))
      (node (ref "D8") (pin "3") (pinfunction "A_3") (pintype "passive"))
      (node (ref "L1") (pin "1") (pinfunction "1_1") (pintype "passive"))
      (node (ref "P2") (pin "5") (pinfunction "5_5") (pintype "passive"))
      (node (ref "R13") (pin "2") (pinfunction "2_2") (pintype "passive"))
      (node (ref "R20") (pin "2") (pinfunction "2_2") (pintype "passive"))
      (node (ref "R26") (pin "1") (pinfunction "1_1") (pintype "passive"))
      (node (ref "TP7") (pin "1") (pinfunction "TP_1") (pintype "passive"))
      (node (ref "U1") (pin "2") (pinfunction "VCC_2") (pintype "power_in"))
      (node (ref "U4") (pin "3") (pinfunction "VCC_3") (pintype "power_in"))
      (node (ref "U5") (pin "21") (pinfunction "VDD_IOB_21") (pintype "passive"))
      (node (ref "U5") (pin "34") (pinfunction "VDD_IO_34") (pintype "passive"))
      (node (ref "U5") (pin "48") (pinfunction "VDD_IO_48") (pintype "passive"))
      (node (ref "U5") (pin "56") (pinfunction "VDD_IO_56") (pintype "passive"))
      (node (ref "U6") (pin "3") (pinfunction "VCC_3") (pintype "power_in"))
    )
    (net (code "39") (name "5V") (class "Default")
      (node (ref "D8") (pin "2") (pinfunction "A_2") (pintype "passive"))
      (node (ref "P1") (pin "1") (pinfunction "1_1") (pintype "passive"))
      (node (ref "R12") (pin "2") (pinfunction "2_2") (pintype "passive"))
      (node (ref "TP4") (pin "1") (pinfunction "TP_1") (pintype "passive"))
    )
    (net (code "40") (name "GND") (class "Default")
      (node (ref "C10") (pin "1") (pinfunction "1_1") (pintype "passive"))
      (node (ref "C11") (pin "2") (pinfunction "2_2") (pintype "passive"))
      (node (ref "C12") (pin "2") (pinfunction "2_2") (pintype "passive"))
      (node (ref "C13") (pin "2") (pinfunction "2_2") (pintype "passive"))
      (node (ref "C14") (pin "2") (pinfunction "2_2") (pintype "passive"))
      (node (ref "C15") (pin "2") (pinfunction "2_2") (pintype "passive"))
      (node (ref "C16") (pin "2") (pinfunction "2_2") (pintype "passive"))
      (node (ref "C17") (pin "2") (pinfunction "2_2") (pintype "passive"))
      (node (ref "C3") (pin "2") (pinfunction "2_2") (pintype "passive"))
      (node (ref "C4") (pin "1") (pinfunction "1_1") (pintype "passive"))
      (node (ref "C5") (pin "2") (pinfunction "2_2") (pintype "passive"))
      (node (ref "C6") (pin "2") (pinfunction "2_2") (pintype "passive"))
      (node (ref "C7") (pin "2") (pinfunction "2_2") (pintype "passive"))
      (node (ref "C8") (pin "1") (pinfunction "1_1") (pintype "passive"))
      (node (ref "C9") (pin "2") (pinfunction "2_2") (pintype "passive"))
      (node (ref "D1") (pin "1") (pinfunction "K_1") (pintype "passive"))
      (node (ref "D1") (pin "4") (pinfunction "K_4") (pintype "passive"))
      (node (ref "P1") (pin "4") (pinfunction "4_4") (pintype "passive"))
      (node (ref "P1") (pin "MP1") (pinfunction "MP1_MP1") (pintype "passive"))
      (node (ref "P1") (pin "MP2") (pinfunction "MP2_MP2") (pintype "passive"))
      (node (ref "P2") (pin "6") (pinfunction "6_6") (pintype "passive"))
      (node (ref "P2") (pin "S1") (pinfunction "SHIELD_S1") (pintype "passive"))
      (node (ref "P2") (pin "S2") (pinfunction "SHIELD_S2") (pintype "passive"))
      (node (ref "R16") (pin "1") (pinfunction "1_1") (pintype "passive"))
      (node (ref "R17") (pin "1") (pinfunction "1_1") (pintype "passive"))
      (node (ref "R18") (pin "1") (pinfunction "1_1") (pintype "passive"))
      (node (ref "R19") (pin "1") (pinfunction "1_1") (pintype "passive"))
      (node (ref "R27") (pin "2") (pinfunction "2_2") (pintype "passive"))
      (node (ref "R28") (pin "2") (pinfunction "2_2") (pintype "passive"))
      (node (ref "SW1") (pin "2") (pinfunction "2_2") (pintype "passive"))
      (node (ref "TP8") (pin "1") (pinfunction "TP_1") (pintype "passive"))
      (node (ref "TP9") (pin "1") (pinfunction "TP_1") (pintype "passive"))
      (node (ref "U1") (pin "11") (pinfunction "GND_11") (pintype "power_in"))
      (node (ref "U4") (pin "2") (pinfunction "GND_2") (pintype "power_in"))
      (node (ref "U5") (pin "22") (pinfunction "GND_22") (pintype "passive"))
      (node (ref "U5") (pin "33") (pinfunction "GND_33") (pintype "passive"))
      (node (ref "U5") (pin "47") (pinfunction "GND_47") (pintype "passive"))
      (node (ref "U5") (pin "54") (pinfunction "GND_54") (pintype "passive"))
      (node (ref "U5") (pin "65") (pinfunction "GND_65") (pintype "passive"))
      (node (ref "U5") (pin "7") (pinfunction "GND_ANA_7") (pintype "passive"))
      (node (ref "U6") (pin "2") (pinfunction "GND_2") (pintype "power_in"))
    )
    (net (code "41") (name "Net-(C13-Pad1)") (class "Default")
      (node (ref "C13") (pin "1") (pinfunction "1_1") (pintype "passive"))
      (node (ref "Y1") (pin "2") (pinfunction "GND_2") (pintype "power_in"))
    )
    (net (code "42") (name "Net-(C14-Pad1)") (class "Default")
      (node (ref "C14") (pin "1") (pinfunction "1_1") (pintype "passive"))
      (node (ref "Y1") (pin "4") (pinfunction "GND_4") (pintype "power_in"))
    )
    (net (code "43") (name "Net-(D1-A-Pad2)") (class "Default")
      (node (ref "D1") (pin "2") (pinfunction "A_2") (pintype "passive"))
      (node (ref "R1") (pin "2") (pinfunction "2_2") (pintype "passive"))
    )
    (net (code "44") (name "Net-(D1-A-Pad3)") (class "Default")
      (node (ref "D1") (pin "3") (pinfunction "A_3") (pintype "passive"))
      (node (ref "R3") (pin "2") (pinfunction "2_2") (pintype "passive"))
    )
    (net (code "45") (name "Net-(D7-K-Pad1)") (class "Default")
      (node (ref "D7") (pin "1") (pinfunction "K_1") (pintype "passive"))
      (node (ref "R23") (pin "1") (pinfunction "1_1") (pintype "passive"))
    )
    (net (code "46") (name "Net-(D7-K-Pad4)") (class "Default")
      (node (ref "D7") (pin "4") (pinfunction "K_4") (pintype "passive"))
      (node (ref "R24") (pin "1") (pinfunction "1_1") (pintype "passive"))
    )
    (net (code "47") (name "Net-(D8-K-Pad1)") (class "Default")
      (node (ref "D8") (pin "1") (pinfunction "K_1") (pintype "passive"))
      (node (ref "R27") (pin "1") (pinfunction "1_1") (pintype "passive"))
    )
    (net (code "48") (name "Net-(D8-K-Pad4)") (class "Default")
      (node (ref "D8") (pin "4") (pinfunction "K_4") (pintype "passive"))
      (node (ref "R28") (pin "1") (pinfunction "1_1") (pintype "passive"))
    )
    (net (code "49") (name "Net-(R25-Pad2)") (class "Default")
      (node (ref "R25") (pin "2") (pinfunction "2_2") (pintype "passive"))
      (node (ref "SW1") (pin "1") (pinfunction "1_1") (pintype "passive"))
    )
    (net (code "50") (name "Net-(U1A-1IN+)") (class "Default")
      (node (ref "R2") (pin "1") (pinfunction "1_1") (pintype "passive"))
      (node (ref "U1") (pin "1") (pinfunction "1IN+_1") (pintype "input"))
    )
    (net (code "51") (name "Net-(U1A-1IN-)") (class "Default")
      (node (ref "R1") (pin "1") (pinfunction "1_1") (pintype "passive"))
      (node (ref "U1") (pin "15") (pinfunction "1OUT_15") (pintype "output"))
      (node (ref "U1") (pin "16") (pinfunction "1IN-_16") (pintype "input"))
    )
    (net (code "52") (name "Net-(U1B-2IN+)") (class "Default")
      (node (ref "R63") (pin "1") (pinfunction "1_1") (pintype "passive"))
      (node (ref "U1") (pin "4") (pinfunction "2IN+_4") (pintype "input"))
    )
    (net (code "53") (name "Net-(U1B-2IN-)") (class "Default")
      (node (ref "R3") (pin "1") (pinfunction "1_1") (pintype "passive"))
      (node (ref "U1") (pin "5") (pinfunction "2IN-_5") (pintype "input"))
      (node (ref "U1") (pin "6") (pinfunction "2OUT_6") (pintype "output"))
    )
    (net (code "54") (name "Net-(U5A-VDD_CORE)") (class "Default")
      (node (ref "C4") (pin "2") (pinfunction "2_2") (pintype "passive"))
      (node (ref "C5") (pin "1") (pinfunction "1_1") (pintype "passive"))
      (node (ref "L2") (pin "2") (pinfunction "2_2") (pintype "passive"))
      (node (ref "U5") (pin "53") (pinfunction "VDD_CORE_53") (pintype "passive"))
    )
    (net (code "55") (name "Net-(U5A-VSW)") (class "Default")
      (node (ref "L2") (pin "1") (pinfunction "1_1") (pintype "passive"))
      (node (ref "U5") (pin "55") (pinfunction "VSW_55") (pintype "passive"))
    )
    (net (code "56") (name "VCC") (class "Default")
      (node (ref "R14") (pin "2") (pinfunction "2_2") (pintype "passive"))
      (node (ref "TP5") (pin "1") (pinfunction "TP_1") (pintype "passive"))
    )
    (net (code "57") (name "unconnected-(U4-S-Pad8)") (class "Default")
      (node (ref "U4") (pin "8") (pinfunction "S_8") (pintype "input+no_connect"))
    )
    (net (code "58") (name "unconnected-(U4-SHDN-Pad5)") (class "Default")
      (node (ref "U4") (pin "5") (pinfunction "SHDN_5") (pintype "input+no_connect"))
    )
    (net (code "59") (name "unconnected-(U5A-PA_10-Pad19)") (class "Default")
      (node (ref "U5") (pin "19") (pinfunction "PA_10_19") (pintype "passive"))
    )
    (net (code "60") (name "unconnected-(U5A-PA_11-Pad20)") (class "Default")
      (node (ref "U5") (pin "20") (pinfunction "PA_11_20") (pintype "passive"))
    )
    (net (code "61") (name "unconnected-(U5A-PA_12-Pad29)") (class "Default")
      (node (ref "U5") (pin "29") (pinfunction "PA_12_29") (pintype "passive"))
    )
    (net (code "62") (name "unconnected-(U5A-PA_13-Pad30)") (class "Default")
      (node (ref "U5") (pin "30") (pinfunction "PA_13_30") (pintype "passive"))
    )
    (net (code "63") (name "unconnected-(U5A-PA_16-Pad35)") (class "Default")
      (node (ref "U5") (pin "35") (pinfunction "PA_16_35") (pintype "passive"))
    )
    (net (code "64") (name "unconnected-(U5A-PA_17-Pad36)") (class "Default")
      (node (ref "U5") (pin "36") (pinfunction "PA_17_36") (pintype "passive"))
    )
    (net (code "65") (name "unconnected-(U5A-PA_18-Pad37)") (class "Default")
      (node (ref "U5") (pin "37") (pinfunction "PA_18_37") (pintype "passive"))
    )
    (net (code "66") (name "unconnected-(U5A-PA_19-Pad38)") (class "Default")
      (node (ref "U5") (pin "38") (pinfunction "PA_19_38") (pintype "passive"))
    )
    (net (code "67") (name "unconnected-(U5A-PA_20-Pad41)") (class "Default")
      (node (ref "U5") (pin "41") (pinfunction "PA_20_41") (pintype "passive"))
    )
    (net (code "68") (name "unconnected-(U5A-PA_21-Pad42)") (class "Default")
      (node (ref "U5") (pin "42") (pinfunction "PA_21_42") (pintype "passive"))
    )
    (net (code "69") (name "unconnected-(U5A-PA_21-Pad42)_1") (class "Default")
      (node (ref "U5") (pin "42") (pinfunction "PA_21_42") (pintype "passive"))
    )
    (net (code "70") (name "unconnected-(U5A-PA_24-Pad45)") (class "Default")
      (node (ref "U5") (pin "45") (pinfunction "PA_24_45") (pintype "passive"))
    )
    (net (code "71") (name "unconnected-(U5A-PA_25-Pad46)") (class "Default")
      (node (ref "U5") (pin "46") (pinfunction "PA_25_46") (pintype "passive"))
    )
    (net (code "72") (name "unconnected-(U5A-PA_27-Pad51)") (class "Default")
      (node (ref "U5") (pin "51") (pinfunction "PA_27_51") (pintype "passive"))
    )
    (net (code "73") (name "unconnected-(U5A-PB_10-Pad23)") (class "Default")
      (node (ref "U5") (pin "23") (pinfunction "PB_10_23") (pintype "passive"))
    )
    (net (code "74") (name "unconnected-(U5A-PB_11-Pad24)") (class "Default")
      (node (ref "U5") (pin "24") (pinfunction "PB_11_24") (pintype "passive"))
    )
    (net (code "75") (name "unconnected-(U5A-PB_12-Pad25)") (class "Default")
      (node (ref "U5") (pin "25") (pinfunction "PB_12_25") (pintype "passive"))
    )
    (net (code "76") (name "unconnected-(U5A-PB_13-Pad26)") (class "Default")
      (node (ref "U5") (pin "26") (pinfunction "PB_13_26") (pintype "passive"))
    )
    (net (code "77") (name "unconnected-(U5A-PB_16-Pad39)") (class "Default")
      (node (ref "U5") (pin "39") (pinfunction "PB_16_39") (pintype "passive"))
    )
    (net (code "78") (name "unconnected-(U5A-PB_17-Pad40)") (class "Default")
      (node (ref "U5") (pin "40") (pinfunction "PB_17_40") (pintype "passive"))
    )
    (net (code "79") (name "unconnected-(U5A-PB_22-Pad49)") (class "Default")
      (node (ref "U5") (pin "49") (pinfunction "PB_22_49") (pintype "passive"))
    )
    (net (code "80") (name "unconnected-(U5A-PB_23-Pad50)") (class "Default")
      (node (ref "U5") (pin "50") (pinfunction "PB_23_50") (pintype "passive"))
    )
    (net (code "81") (name "unconnected-(U5A-PB_31-Pad60)") (class "Default")
      (node (ref "U5") (pin "60") (pinfunction "PB_31_60") (pintype "passive"))
    )
    (net (code "82") (name "unconnected-(U6-S-Pad8)") (class "Default")
      (node (ref "U6") (pin "8") (pinfunction "S_8") (pintype "input+no_connect"))
    )
    (net (code "83") (name "unconnected-(U6-SHDN-Pad5)") (class "Default")
      (node (ref "U6") (pin "5") (pinfunction "SHDN_5") (pintype "input+no_connect"))
    )
  )
)
